# joystick-schematic.net
KiCad netlist of a schematic drawn in EasyEDA
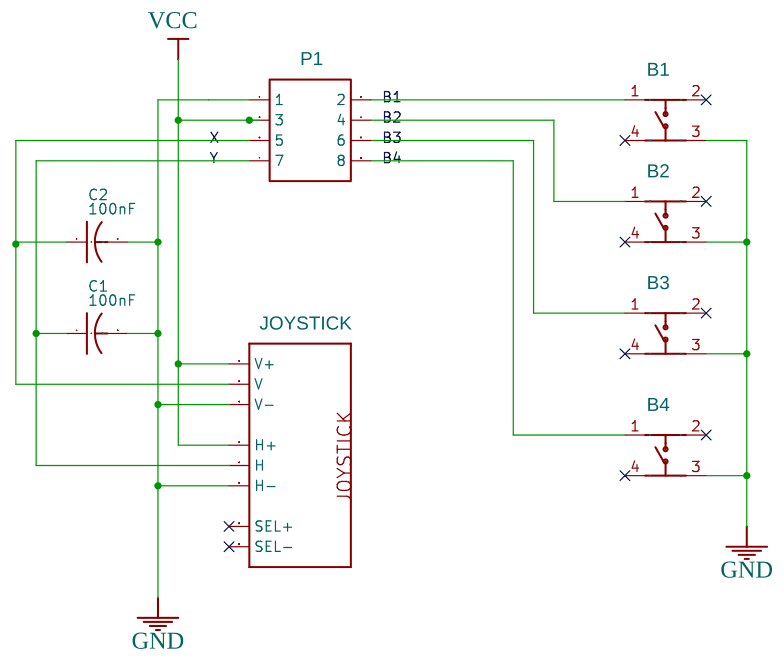
[diagram p0: schematic sheet]

(export (version "E")
  (design (tool "Eeschema 10.0.6"))
  (components
    (comp (ref "C1")
      (value "100nF")
      (fields (field (name "BOM_Supplier Part") "C154503"))
      (libsource (lib "") (part "Unknown_440_460"))
    )
    (comp (ref "C2")
      (value "100nF")
      (fields (field (name "BOM_Supplier Part") "C154503"))
      (libsource (lib "") (part "Unknown_440_415"))
    )
    (comp (ref "KEY1")
      (value "B1")
      (fields (field (name "BOM_Supplier Part") "C110153"))
      (libsource (lib "") (part "Unknown_725_355"))
    )
    (comp (ref "KEY2")
      (value "B2")
      (fields (field (name "BOM_Supplier Part") "C110153"))
      (libsource (lib "") (part "Unknown_725_405"))
    )
    (comp (ref "KEY3")
      (value "B3")
      (fields (field (name "BOM_Supplier Part") "C110153"))
      (libsource (lib "") (part "Unknown_725_460"))
    )
    (comp (ref "KEY4")
      (value "B4")
      (fields (field (name "BOM_Supplier Part") "C110153"))
      (libsource (lib "") (part "Unknown_725_520"))
    )
    (comp (ref "P1")
      (value "HDR-IDC-2.54-2X4P")
      (fields
        (field (name "BOM_Manufacturer Part") "IDC Box 2X4 2.54MM")
        (field (name "BOM_Supplier Part") "C9135")
      )
      (libsource (lib "") (part "Unknown_550_360"))
    )
    (comp (ref "U1")
      (value "JOYSTICK")
      (fields (field (name "BOM_Supplier Part") "1568-1526-ND"))
      (libsource (lib "") (part "Unknown_540_520"))
    )
  )
  (nets
    (net (code "1") (name "/B1") (class "Default")
      (node (ref "KEY1") (pin "1") (pinfunction "1_1") (pintype "unspecified"))
      (node (ref "P1") (pin "2") (pinfunction "2_2") (pintype "unspecified"))
    )
    (net (code "2") (name "/B2") (class "Default")
      (node (ref "KEY2") (pin "1") (pinfunction "1_1") (pintype "unspecified"))
      (node (ref "P1") (pin "4") (pinfunction "4_4") (pintype "unspecified"))
    )
    (net (code "3") (name "/B3") (class "Default")
      (node (ref "KEY3") (pin "1") (pinfunction "1_1") (pintype "unspecified"))
      (node (ref "P1") (pin "6") (pinfunction "6_6") (pintype "unspecified"))
    )
    (net (code "4") (name "/B4") (class "Default")
      (node (ref "KEY4") (pin "1") (pinfunction "1_1") (pintype "unspecified"))
      (node (ref "P1") (pin "8") (pinfunction "8_8") (pintype "unspecified"))
    )
    (net (code "5") (name "/X") (class "Default")
      (node (ref "C2") (pin "1") (pinfunction "1_1") (pintype "bidirectional"))
      (node (ref "P1") (pin "5") (pinfunction "5_5") (pintype "unspecified"))
      (node (ref "U1") (pin "V2") (pinfunction "V_V2") (pintype "unspecified"))
    )
    (net (code "6") (name "/Y") (class "Default")
      (node (ref "C1") (pin "1") (pinfunction "1_1") (pintype "bidirectional"))
      (node (ref "P1") (pin "7") (pinfunction "7_7") (pintype "unspecified"))
      (node (ref "U1") (pin "H2") (pinfunction "H_H2") (pintype "unspecified"))
    )
    (net (code "7") (name "GND") (class "Default")
      (node (ref "C1") (pin "2") (pinfunction "2_2") (pintype "bidirectional"))
      (node (ref "C2") (pin "2") (pinfunction "2_2") (pintype "bidirectional"))
      (node (ref "KEY1") (pin "3") (pinfunction "3_3") (pintype "unspecified"))
      (node (ref "KEY2") (pin "3") (pinfunction "3_3") (pintype "unspecified"))
      (node (ref "KEY3") (pin "3") (pinfunction "3_3") (pintype "unspecified"))
      (node (ref "KEY4") (pin "3") (pinfunction "3_3") (pintype "unspecified"))
      (node (ref "P1") (pin "1") (pinfunction "1_1") (pintype "unspecified"))
      (node (ref "U1") (pin "H3") (pinfunction "H-_H3") (pintype "unspecified"))
      (node (ref "U1") (pin "V3") (pinfunction "V-_V3") (pintype "unspecified"))
    )
    (net (code "8") (name "VCC") (class "Default")
      (node (ref "P1") (pin "3") (pinfunction "3_3") (pintype "unspecified"))
      (node (ref "U1") (pin "H1") (pinfunction "H+_H1") (pintype "unspecified"))
      (node (ref "U1") (pin "V1") (pinfunction "V+_V1") (pintype "unspecified"))
    )
    (net (code "9") (name "unconnected-(KEY1-Pad2)") (class "Default")
      (node (ref "KEY1") (pin "2") (pinfunction "2_2") (pintype "unspecified+no_connect"))
    )
    (net (code "10") (name "unconnected-(KEY1-Pad4)") (class "Default")
      (node (ref "KEY1") (pin "4") (pinfunction "4_4") (pintype "unspecified+no_connect"))
    )
    (net (code "11") (name "unconnected-(KEY2-Pad2)") (class "Default")
      (node (ref "KEY2") (pin "2") (pinfunction "2_2") (pintype "unspecified+no_connect"))
    )
    (net (code "12") (name "unconnected-(KEY2-Pad4)") (class "Default")
      (node (ref "KEY2") (pin "4") (pinfunction "4_4") (pintype "unspecified+no_connect"))
    )
    (net (code "13") (name "unconnected-(KEY3-Pad2)") (class "Default")
      (node (ref "KEY3") (pin "2") (pinfunction "2_2") (pintype "unspecified+no_connect"))
    )
    (net (code "14") (name "unconnected-(KEY3-Pad4)") (class "Default")
      (node (ref "KEY3") (pin "4") (pinfunction "4_4") (pintype "unspecified+no_connect"))
    )
    (net (code "15") (name "unconnected-(KEY4-Pad2)") (class "Default")
      (node (ref "KEY4") (pin "2") (pinfunction "2_2") (pintype "unspecified+no_connect"))
    )
    (net (code "16") (name "unconnected-(KEY4-Pad4)") (class "Default")
      (node (ref "KEY4") (pin "4") (pinfunction "4_4") (pintype "unspecified+no_connect"))
    )
    (net (code "17") (name "unconnected-(U1-SEL+-PadB1A)") (class "Default")
      (node (ref "U1") (pin "B1A") (pinfunction "SEL+_B1A") (pintype "unspecified+no_connect"))
    )
    (net (code "18") (name "unconnected-(U1-SEL--PadB2A)") (class "Default")
      (node (ref "U1") (pin "B2A") (pinfunction "SEL-_B2A") (pintype "unspecified+no_connect"))
    )
  )
)
